# tick-controller-mk-2.net
KiCad netlist of a schematic drawn in EAGLE
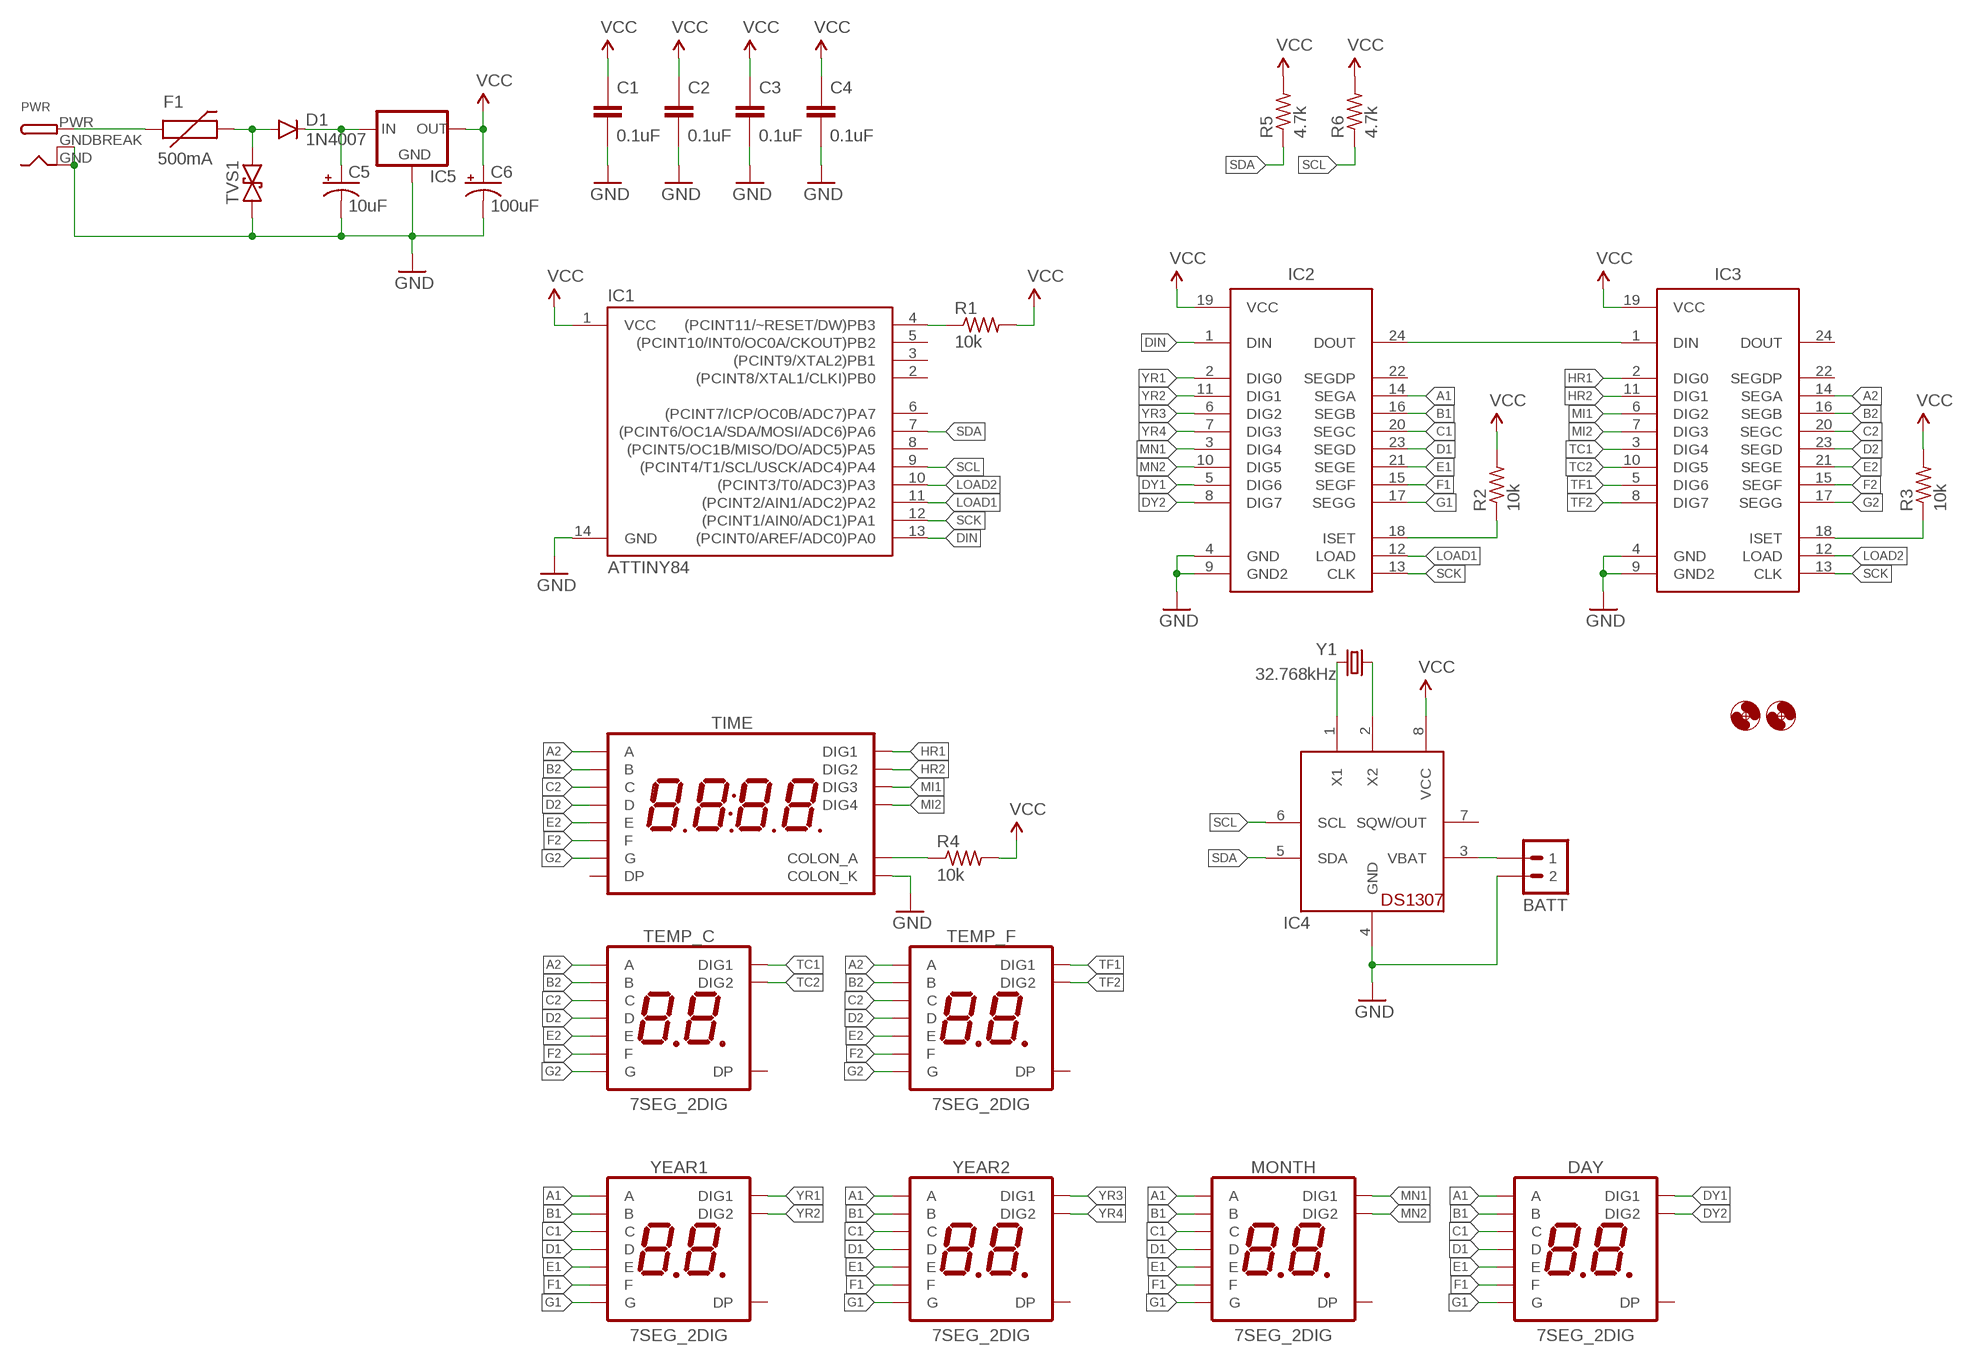
[diagram p0: schematic, sheet 1]

(export (version "E")
  (design (tool "Eeschema 10.0.6"))
  (components
    (comp (ref "BATT")
      (value "M02JST-PTH-VERT")
      (footprint "eagle-import:JST-2-PH-VERT-PTH")
      (libsource (lib "eagle-import") (part "M02JST-PTH-VERT"))
    )
    (comp (ref "C1")
      (value "0.1uF")
      (footprint "eagle-import:C025-024X044")
      (libsource (lib "eagle-import") (part "CAPACITOR-CERAMIC025-024X044"))
    )
    (comp (ref "C2")
      (value "0.1uF")
      (footprint "eagle-import:C025-024X044")
      (libsource (lib "eagle-import") (part "CAPACITOR-CERAMIC025-024X044"))
    )
    (comp (ref "C3")
      (value "0.1uF")
      (footprint "eagle-import:C025-024X044")
      (libsource (lib "eagle-import") (part "CAPACITOR-CERAMIC025-024X044"))
    )
    (comp (ref "C4")
      (value "0.1uF")
      (footprint "eagle-import:C025-024X044")
      (libsource (lib "eagle-import") (part "CAPACITOR-CERAMIC025-024X044"))
    )
    (comp (ref "C5")
      (value "10uF")
      (footprint "eagle-import:E2-5")
      (libsource (lib "eagle-import") (part "CAPACITOR-POLARIZEDE2-5"))
    )
    (comp (ref "C6")
      (value "100uF")
      (footprint "eagle-import:E2-5")
      (libsource (lib "eagle-import") (part "CAPACITOR-POLARIZEDE2-5"))
    )
    (comp (ref "D1")
      (value "1N4007")
      (footprint "eagle-import:DIODE-10.16MM")
      (libsource (lib "eagle-import") (part "DIODEPTH-10.68MM"))
    )
    (comp (ref "DAY")
      (value "7SEG_2DIG")
      (footprint "eagle-import:7SEG_2DIG_14MM")
      (libsource (lib "eagle-import") (part "7SEG_2DIG"))
    )
    (comp (ref "F1")
      (value "500mA")
      (footprint "eagle-import:PTC")
      (libsource (lib "eagle-import") (part "PTCPTH"))
    )
    (comp (ref "H1")
      (value "HOLE#2")
      (footprint "eagle-import:HOLE-#2")
      (libsource (lib "eagle-import") (part "HOLE#2"))
    )
    (comp (ref "H2")
      (value "HOLE#2")
      (footprint "eagle-import:HOLE-#2")
      (libsource (lib "eagle-import") (part "HOLE#2"))
    )
    (comp (ref "IC1")
      (value "ATTINY84")
      (footprint "eagle-import:DIL14")
      (libsource (lib "eagle-import") (part "ATTINY84ATTINY84-20PU"))
    )
    (comp (ref "IC2")
      (value "MAX7219")
      (footprint "eagle-import:DIL24")
      (libsource (lib "eagle-import") (part "MAX7219DIP"))
    )
    (comp (ref "IC3")
      (value "MAX7219")
      (footprint "eagle-import:DIL24")
      (libsource (lib "eagle-import") (part "MAX7219DIP"))
    )
    (comp (ref "IC4")
      (value "DS1307")
      (footprint "eagle-import:DIL08")
      (libsource (lib "eagle-import") (part "DS1307"))
    )
    (comp (ref "IC5")
      (value "L7805")
      (footprint "eagle-import:78XXL")
      (libsource (lib "eagle-import") (part "V_REG_78XXSIDE"))
    )
    (comp (ref "MONTH")
      (value "7SEG_2DIG")
      (footprint "eagle-import:7SEG_2DIG_14MM")
      (libsource (lib "eagle-import") (part "7SEG_2DIG"))
    )
    (comp (ref "PWR")
      (value "DCBARRELPTH")
      (footprint "eagle-import:DCJACK_2MM_PTH")
      (libsource (lib "eagle-import") (part "DCBARRELPTH"))
    )
    (comp (ref "R1")
      (value "10k")
      (footprint "eagle-import:RESISTOR-AXIAL-PTH-5.08MM")
      (libsource (lib "eagle-import") (part "RESISTORPTH-AXIAL-5.08MM"))
    )
    (comp (ref "R2")
      (value "10k")
      (footprint "eagle-import:RESISTOR-AXIAL-PTH-5.08MM")
      (libsource (lib "eagle-import") (part "RESISTORPTH-AXIAL-5.08MM"))
    )
    (comp (ref "R3")
      (value "10k")
      (footprint "eagle-import:RESISTOR-AXIAL-PTH-5.08MM")
      (libsource (lib "eagle-import") (part "RESISTORPTH-AXIAL-5.08MM"))
    )
    (comp (ref "R4")
      (value "10k")
      (footprint "eagle-import:RESISTOR-AXIAL-PTH-5.08MM")
      (libsource (lib "eagle-import") (part "RESISTORPTH-AXIAL-5.08MM"))
    )
    (comp (ref "R5")
      (value "4.7k")
      (footprint "eagle-import:RESISTOR-AXIAL-PTH-5.08MM")
      (libsource (lib "eagle-import") (part "RESISTORPTH-AXIAL-5.08MM"))
    )
    (comp (ref "R6")
      (value "4.7k")
      (footprint "eagle-import:RESISTOR-AXIAL-PTH-5.08MM")
      (libsource (lib "eagle-import") (part "RESISTORPTH-AXIAL-5.08MM"))
    )
    (comp (ref "TEMP_C")
      (value "7SEG_2DIG")
      (footprint "eagle-import:7SEG_2DIG_14MM")
      (libsource (lib "eagle-import") (part "7SEG_2DIG"))
    )
    (comp (ref "TEMP_F")
      (value "7SEG_2DIG")
      (footprint "eagle-import:7SEG_2DIG_14MM")
      (libsource (lib "eagle-import") (part "7SEG_2DIG"))
    )
    (comp (ref "TIME")
      (value "7SED_4DIGIT_14MM14.2MM-CC")
      (footprint "eagle-import:7SEG_4DIG")
      (libsource (lib "eagle-import") (part "7SED_4DIGIT_14MM14.2MM-CC"))
    )
    (comp (ref "TVS1")
      (value "TVSDO-41-TVS-BIDIRECTIONAL")
      (footprint "eagle-import:DO-41-TVS")
      (libsource (lib "eagle-import") (part "TVSDO-41-TVS-BIDIRECTIONAL"))
    )
    (comp (ref "Y1")
      (value "32.768kHz")
      (footprint "eagle-import:TC26H")
      (libsource (lib "eagle-import") (part "CRYSTALTC26H"))
    )
    (comp (ref "YEAR1")
      (value "7SEG_2DIG")
      (footprint "eagle-import:7SEG_2DIG_14MM")
      (libsource (lib "eagle-import") (part "7SEG_2DIG"))
    )
    (comp (ref "YEAR2")
      (value "7SEG_2DIG")
      (footprint "eagle-import:7SEG_2DIG_14MM")
      (libsource (lib "eagle-import") (part "7SEG_2DIG"))
    )
  )
  (nets
    (net (code "1") (name "A1") (class "Default")
      (node (ref "DAY") (pin "4") (pinfunction "A_4") (pintype "passive"))
      (node (ref "IC2") (pin "14") (pinfunction "SEGA_14") (pintype "bidirectional"))
      (node (ref "MONTH") (pin "4") (pinfunction "A_4") (pintype "passive"))
      (node (ref "YEAR1") (pin "4") (pinfunction "A_4") (pintype "passive"))
      (node (ref "YEAR2") (pin "4") (pinfunction "A_4") (pintype "passive"))
    )
    (net (code "2") (name "A2") (class "Default")
      (node (ref "IC3") (pin "14") (pinfunction "SEGA_14") (pintype "bidirectional"))
      (node (ref "TEMP_C") (pin "4") (pinfunction "A_4") (pintype "passive"))
      (node (ref "TEMP_F") (pin "4") (pinfunction "A_4") (pintype "passive"))
      (node (ref "TIME") (pin "P$13") (pinfunction "A_P$13") (pintype "passive"))
    )
    (net (code "3") (name "B1") (class "Default")
      (node (ref "DAY") (pin "3") (pinfunction "B_3") (pintype "passive"))
      (node (ref "IC2") (pin "16") (pinfunction "SEGB_16") (pintype "bidirectional"))
      (node (ref "MONTH") (pin "3") (pinfunction "B_3") (pintype "passive"))
      (node (ref "YEAR1") (pin "3") (pinfunction "B_3") (pintype "passive"))
      (node (ref "YEAR2") (pin "3") (pinfunction "B_3") (pintype "passive"))
    )
    (net (code "4") (name "B2") (class "Default")
      (node (ref "IC3") (pin "16") (pinfunction "SEGB_16") (pintype "bidirectional"))
      (node (ref "TEMP_C") (pin "3") (pinfunction "B_3") (pintype "passive"))
      (node (ref "TEMP_F") (pin "3") (pinfunction "B_3") (pintype "passive"))
      (node (ref "TIME") (pin "P$9") (pinfunction "B_P$9") (pintype "passive"))
    )
    (net (code "5") (name "C1") (class "Default")
      (node (ref "DAY") (pin "9") (pinfunction "C_9") (pintype "passive"))
      (node (ref "IC2") (pin "20") (pinfunction "SEGC_20") (pintype "bidirectional"))
      (node (ref "MONTH") (pin "9") (pinfunction "C_9") (pintype "passive"))
      (node (ref "YEAR1") (pin "9") (pinfunction "C_9") (pintype "passive"))
      (node (ref "YEAR2") (pin "9") (pinfunction "C_9") (pintype "passive"))
    )
    (net (code "6") (name "C2") (class "Default")
      (node (ref "IC3") (pin "20") (pinfunction "SEGC_20") (pintype "bidirectional"))
      (node (ref "TEMP_C") (pin "9") (pinfunction "C_9") (pintype "passive"))
      (node (ref "TEMP_F") (pin "9") (pinfunction "C_9") (pintype "passive"))
      (node (ref "TIME") (pin "P$4") (pinfunction "C_P$4") (pintype "passive"))
    )
    (net (code "7") (name "D1") (class "Default")
      (node (ref "DAY") (pin "8") (pinfunction "D_8") (pintype "passive"))
      (node (ref "IC2") (pin "23") (pinfunction "SEGD_23") (pintype "bidirectional"))
      (node (ref "MONTH") (pin "8") (pinfunction "D_8") (pintype "passive"))
      (node (ref "YEAR1") (pin "8") (pinfunction "D_8") (pintype "passive"))
      (node (ref "YEAR2") (pin "8") (pinfunction "D_8") (pintype "passive"))
    )
    (net (code "8") (name "D2") (class "Default")
      (node (ref "IC3") (pin "23") (pinfunction "SEGD_23") (pintype "bidirectional"))
      (node (ref "TEMP_C") (pin "8") (pinfunction "D_8") (pintype "passive"))
      (node (ref "TEMP_F") (pin "8") (pinfunction "D_8") (pintype "passive"))
      (node (ref "TIME") (pin "P$2") (pinfunction "D_P$2") (pintype "passive"))
    )
    (net (code "9") (name "DIN") (class "Default")
      (node (ref "IC1") (pin "13") (pinfunction "(PCINT0/AREF/ADC0)PA0_13") (pintype "bidirectional"))
      (node (ref "IC2") (pin "1") (pinfunction "DIN_1") (pintype "bidirectional"))
    )
    (net (code "10") (name "DY1") (class "Default")
      (node (ref "DAY") (pin "5") (pinfunction "DIG1_5") (pintype "passive"))
      (node (ref "IC2") (pin "5") (pinfunction "DIG6_5") (pintype "bidirectional"))
    )
    (net (code "11") (name "DY2") (class "Default")
      (node (ref "DAY") (pin "10") (pinfunction "DIG2_10") (pintype "passive"))
      (node (ref "IC2") (pin "8") (pinfunction "DIG7_8") (pintype "bidirectional"))
    )
    (net (code "12") (name "E1") (class "Default")
      (node (ref "DAY") (pin "6") (pinfunction "E_6") (pintype "passive"))
      (node (ref "IC2") (pin "21") (pinfunction "SEGE_21") (pintype "bidirectional"))
      (node (ref "MONTH") (pin "6") (pinfunction "E_6") (pintype "passive"))
      (node (ref "YEAR1") (pin "6") (pinfunction "E_6") (pintype "passive"))
      (node (ref "YEAR2") (pin "6") (pinfunction "E_6") (pintype "passive"))
    )
    (net (code "13") (name "E2") (class "Default")
      (node (ref "IC3") (pin "21") (pinfunction "SEGE_21") (pintype "bidirectional"))
      (node (ref "TEMP_C") (pin "6") (pinfunction "E_6") (pintype "passive"))
      (node (ref "TEMP_F") (pin "6") (pinfunction "E_6") (pintype "passive"))
      (node (ref "TIME") (pin "P$1") (pinfunction "E_P$1") (pintype "passive"))
    )
    (net (code "14") (name "F1") (class "Default")
      (node (ref "DAY") (pin "7") (pinfunction "F_7") (pintype "passive"))
      (node (ref "IC2") (pin "15") (pinfunction "SEGF_15") (pintype "bidirectional"))
      (node (ref "MONTH") (pin "7") (pinfunction "F_7") (pintype "passive"))
      (node (ref "YEAR1") (pin "7") (pinfunction "F_7") (pintype "passive"))
      (node (ref "YEAR2") (pin "7") (pinfunction "F_7") (pintype "passive"))
    )
    (net (code "15") (name "F2") (class "Default")
      (node (ref "IC3") (pin "15") (pinfunction "SEGF_15") (pintype "bidirectional"))
      (node (ref "TEMP_C") (pin "7") (pinfunction "F_7") (pintype "passive"))
      (node (ref "TEMP_F") (pin "7") (pinfunction "F_7") (pintype "passive"))
      (node (ref "TIME") (pin "P$12") (pinfunction "F_P$12") (pintype "passive"))
    )
    (net (code "16") (name "G1") (class "Default")
      (node (ref "DAY") (pin "1") (pinfunction "G_1") (pintype "passive"))
      (node (ref "IC2") (pin "17") (pinfunction "SEGG_17") (pintype "bidirectional"))
      (node (ref "MONTH") (pin "1") (pinfunction "G_1") (pintype "passive"))
      (node (ref "YEAR1") (pin "1") (pinfunction "G_1") (pintype "passive"))
      (node (ref "YEAR2") (pin "1") (pinfunction "G_1") (pintype "passive"))
    )
    (net (code "17") (name "G2") (class "Default")
      (node (ref "IC3") (pin "17") (pinfunction "SEGG_17") (pintype "bidirectional"))
      (node (ref "TEMP_C") (pin "1") (pinfunction "G_1") (pintype "passive"))
      (node (ref "TEMP_F") (pin "1") (pinfunction "G_1") (pintype "passive"))
      (node (ref "TIME") (pin "P$5") (pinfunction "G_P$5") (pintype "passive"))
    )
    (net (code "18") (name "GND") (class "Default")
      (node (ref "BATT") (pin "2") (pinfunction "2_2") (pintype "passive"))
      (node (ref "C1") (pin "2") (pinfunction "2_2") (pintype "passive"))
      (node (ref "C2") (pin "2") (pinfunction "2_2") (pintype "passive"))
      (node (ref "C3") (pin "2") (pinfunction "2_2") (pintype "passive"))
      (node (ref "C4") (pin "2") (pinfunction "2_2") (pintype "passive"))
      (node (ref "C5") (pin "-") (pinfunction "-_-") (pintype "passive"))
      (node (ref "C6") (pin "-") (pinfunction "-_-") (pintype "passive"))
      (node (ref "IC1") (pin "14") (pinfunction "GND_14") (pintype "bidirectional"))
      (node (ref "IC2") (pin "4") (pinfunction "GND_4") (pintype "bidirectional"))
      (node (ref "IC2") (pin "9") (pinfunction "GND2_9") (pintype "bidirectional"))
      (node (ref "IC3") (pin "4") (pinfunction "GND_4") (pintype "bidirectional"))
      (node (ref "IC3") (pin "9") (pinfunction "GND2_9") (pintype "bidirectional"))
      (node (ref "IC4") (pin "4") (pinfunction "GND_4") (pintype "power_in"))
      (node (ref "IC5") (pin "GND") (pinfunction "GND_GND") (pintype "input"))
      (node (ref "PWR") (pin "GND") (pinfunction "GND_GND") (pintype "power_in"))
      (node (ref "PWR") (pin "GNDBREAK") (pinfunction "GNDBREAK_GNDBREAK") (pintype "power_in"))
      (node (ref "TIME") (pin "P$7") (pinfunction "COLON_K_P$7") (pintype "passive"))
      (node (ref "TVS1") (pin "P$1") (pinfunction "1_P$1") (pintype "passive"))
    )
    (net (code "19") (name "HR1") (class "Default")
      (node (ref "IC3") (pin "2") (pinfunction "DIG0_2") (pintype "bidirectional"))
      (node (ref "TIME") (pin "P$14") (pinfunction "DIG1_P$14") (pintype "passive"))
    )
    (net (code "20") (name "HR2") (class "Default")
      (node (ref "IC3") (pin "11") (pinfunction "DIG1_11") (pintype "bidirectional"))
      (node (ref "TIME") (pin "P$11") (pinfunction "DIG2_P$11") (pintype "passive"))
    )
    (net (code "21") (name "LOAD1") (class "Default")
      (node (ref "IC1") (pin "11") (pinfunction "(PCINT2/AIN1/ADC2)PA2_11") (pintype "bidirectional"))
      (node (ref "IC2") (pin "12") (pinfunction "LOAD_12") (pintype "bidirectional"))
    )
    (net (code "22") (name "LOAD2") (class "Default")
      (node (ref "IC1") (pin "10") (pinfunction "(PCINT3/T0/ADC3)PA3_10") (pintype "bidirectional"))
      (node (ref "IC3") (pin "12") (pinfunction "LOAD_12") (pintype "bidirectional"))
    )
    (net (code "23") (name "MI1") (class "Default")
      (node (ref "IC3") (pin "6") (pinfunction "DIG2_6") (pintype "bidirectional"))
      (node (ref "TIME") (pin "P$10") (pinfunction "DIG3_P$10") (pintype "passive"))
    )
    (net (code "24") (name "MI2") (class "Default")
      (node (ref "IC3") (pin "7") (pinfunction "DIG3_7") (pintype "bidirectional"))
      (node (ref "TIME") (pin "P$6") (pinfunction "DIG4_P$6") (pintype "passive"))
    )
    (net (code "25") (name "MN1") (class "Default")
      (node (ref "IC2") (pin "3") (pinfunction "DIG4_3") (pintype "bidirectional"))
      (node (ref "MONTH") (pin "5") (pinfunction "DIG1_5") (pintype "passive"))
    )
    (net (code "26") (name "MN2") (class "Default")
      (node (ref "IC2") (pin "10") (pinfunction "DIG5_10") (pintype "bidirectional"))
      (node (ref "MONTH") (pin "10") (pinfunction "DIG2_10") (pintype "passive"))
    )
    (net (code "27") (name "Net-(C5-Pad+)") (class "Default")
      (node (ref "C5") (pin "+") (pinfunction "+_+") (pintype "passive"))
      (node (ref "D1") (pin "C") (pinfunction "C_C") (pintype "passive"))
      (node (ref "IC5") (pin "IN") (pinfunction "IN_IN") (pintype "input"))
    )
    (net (code "28") (name "Net-(F1-1)") (class "Default")
      (node (ref "F1") (pin "P$1") (pinfunction "1_P$1") (pintype "bidirectional"))
      (node (ref "PWR") (pin "PWR") (pinfunction "PWR_PWR") (pintype "power_in"))
    )
    (net (code "29") (name "Net-(F1-2)") (class "Default")
      (node (ref "D1") (pin "A") (pinfunction "A_A") (pintype "passive"))
      (node (ref "F1") (pin "P$2") (pinfunction "2_P$2") (pintype "bidirectional"))
      (node (ref "TVS1") (pin "P$2") (pinfunction "2_P$2") (pintype "passive"))
    )
    (net (code "30") (name "Net-(IC1-(PCINT11{slash}~{RESET{slash}DW})PB3)") (class "Default")
      (node (ref "IC1") (pin "4") (pinfunction "(PCINT11/~{RESET/DW})PB3_4") (pintype "bidirectional"))
      (node (ref "R1") (pin "P$1") (pinfunction "1_P$1") (pintype "passive"))
    )
    (net (code "31") (name "Net-(IC2-DOUT)") (class "Default")
      (node (ref "IC2") (pin "24") (pinfunction "DOUT_24") (pintype "bidirectional"))
      (node (ref "IC3") (pin "1") (pinfunction "DIN_1") (pintype "bidirectional"))
    )
    (net (code "32") (name "Net-(IC2-ISET)") (class "Default")
      (node (ref "IC2") (pin "18") (pinfunction "ISET_18") (pintype "bidirectional"))
      (node (ref "R2") (pin "P$1") (pinfunction "1_P$1") (pintype "passive"))
    )
    (net (code "33") (name "Net-(IC3-ISET)") (class "Default")
      (node (ref "IC3") (pin "18") (pinfunction "ISET_18") (pintype "bidirectional"))
      (node (ref "R3") (pin "P$1") (pinfunction "1_P$1") (pintype "passive"))
    )
    (net (code "34") (name "Net-(IC4-VBAT)") (class "Default")
      (node (ref "BATT") (pin "1") (pinfunction "1_1") (pintype "passive"))
      (node (ref "IC4") (pin "3") (pinfunction "VBAT_3") (pintype "power_in"))
    )
    (net (code "35") (name "Net-(IC4-X1)") (class "Default")
      (node (ref "IC4") (pin "1") (pinfunction "X1_1") (pintype "passive"))
      (node (ref "Y1") (pin "2") (pinfunction "2_2") (pintype "passive"))
    )
    (net (code "36") (name "Net-(IC4-X2)") (class "Default")
      (node (ref "IC4") (pin "2") (pinfunction "X2_2") (pintype "passive"))
      (node (ref "Y1") (pin "1") (pinfunction "1_1") (pintype "passive"))
    )
    (net (code "37") (name "Net-(R4-1)") (class "Default")
      (node (ref "R4") (pin "P$1") (pinfunction "1_P$1") (pintype "passive"))
      (node (ref "TIME") (pin "P$8") (pinfunction "COLON_A_P$8") (pintype "passive"))
    )
    (net (code "38") (name "SCK") (class "Default")
      (node (ref "IC1") (pin "12") (pinfunction "(PCINT1/AIN0/ADC1)PA1_12") (pintype "bidirectional"))
      (node (ref "IC2") (pin "13") (pinfunction "CLK_13") (pintype "bidirectional"))
      (node (ref "IC3") (pin "13") (pinfunction "CLK_13") (pintype "bidirectional"))
    )
    (net (code "39") (name "SCL") (class "Default")
      (node (ref "IC1") (pin "9") (pinfunction "(PCINT4/T1/SCL/USCK/ADC4)PA4_9") (pintype "bidirectional"))
      (node (ref "IC4") (pin "6") (pinfunction "SCL_6") (pintype "bidirectional"))
      (node (ref "R6") (pin "P$1") (pinfunction "1_P$1") (pintype "passive"))
    )
    (net (code "40") (name "SDA") (class "Default")
      (node (ref "IC1") (pin "7") (pinfunction "(PCINT6/OC1A/SDA/MOSI/ADC6)PA6_7") (pintype "bidirectional"))
      (node (ref "IC4") (pin "5") (pinfunction "SDA_5") (pintype "bidirectional"))
      (node (ref "R5") (pin "P$1") (pinfunction "1_P$1") (pintype "passive"))
    )
    (net (code "41") (name "TC1") (class "Default")
      (node (ref "IC3") (pin "3") (pinfunction "DIG4_3") (pintype "bidirectional"))
      (node (ref "TEMP_C") (pin "5") (pinfunction "DIG1_5") (pintype "passive"))
    )
    (net (code "42") (name "TC2") (class "Default")
      (node (ref "IC3") (pin "10") (pinfunction "DIG5_10") (pintype "bidirectional"))
      (node (ref "TEMP_C") (pin "10") (pinfunction "DIG2_10") (pintype "passive"))
    )
    (net (code "43") (name "TF1") (class "Default")
      (node (ref "IC3") (pin "5") (pinfunction "DIG6_5") (pintype "bidirectional"))
      (node (ref "TEMP_F") (pin "5") (pinfunction "DIG1_5") (pintype "passive"))
    )
    (net (code "44") (name "TF2") (class "Default")
      (node (ref "IC3") (pin "8") (pinfunction "DIG7_8") (pintype "bidirectional"))
      (node (ref "TEMP_F") (pin "10") (pinfunction "DIG2_10") (pintype "passive"))
    )
    (net (code "45") (name "VCC") (class "Default")
      (node (ref "C1") (pin "1") (pinfunction "1_1") (pintype "passive"))
      (node (ref "C2") (pin "1") (pinfunction "1_1") (pintype "passive"))
      (node (ref "C3") (pin "1") (pinfunction "1_1") (pintype "passive"))
      (node (ref "C4") (pin "1") (pinfunction "1_1") (pintype "passive"))
      (node (ref "C6") (pin "+") (pinfunction "+_+") (pintype "passive"))
      (node (ref "IC1") (pin "1") (pinfunction "VCC_1") (pintype "bidirectional"))
      (node (ref "IC2") (pin "19") (pinfunction "VCC_19") (pintype "bidirectional"))
      (node (ref "IC3") (pin "19") (pinfunction "VCC_19") (pintype "bidirectional"))
      (node (ref "IC4") (pin "8") (pinfunction "VCC_8") (pintype "power_in"))
      (node (ref "IC5") (pin "OUT") (pinfunction "OUT_OUT") (pintype "output"))
      (node (ref "R1") (pin "P$2") (pinfunction "2_P$2") (pintype "passive"))
      (node (ref "R2") (pin "P$2") (pinfunction "2_P$2") (pintype "passive"))
      (node (ref "R3") (pin "P$2") (pinfunction "2_P$2") (pintype "passive"))
      (node (ref "R4") (pin "P$2") (pinfunction "2_P$2") (pintype "passive"))
      (node (ref "R5") (pin "P$2") (pinfunction "2_P$2") (pintype "passive"))
      (node (ref "R6") (pin "P$2") (pinfunction "2_P$2") (pintype "passive"))
    )
    (net (code "46") (name "YR1") (class "Default")
      (node (ref "IC2") (pin "2") (pinfunction "DIG0_2") (pintype "bidirectional"))
      (node (ref "YEAR1") (pin "5") (pinfunction "DIG1_5") (pintype "passive"))
    )
    (net (code "47") (name "YR2") (class "Default")
      (node (ref "IC2") (pin "11") (pinfunction "DIG1_11") (pintype "bidirectional"))
      (node (ref "YEAR1") (pin "10") (pinfunction "DIG2_10") (pintype "passive"))
    )
    (net (code "48") (name "YR3") (class "Default")
      (node (ref "IC2") (pin "6") (pinfunction "DIG2_6") (pintype "bidirectional"))
      (node (ref "YEAR2") (pin "5") (pinfunction "DIG1_5") (pintype "passive"))
    )
    (net (code "49") (name "YR4") (class "Default")
      (node (ref "IC2") (pin "7") (pinfunction "DIG3_7") (pintype "bidirectional"))
      (node (ref "YEAR2") (pin "10") (pinfunction "DIG2_10") (pintype "passive"))
    )
    (net (code "50") (name "unconnected-(DAY-DP-Pad2)") (class "Default")
      (node (ref "DAY") (pin "2") (pinfunction "DP_2") (pintype "passive"))
    )
    (net (code "51") (name "unconnected-(IC1-(PCINT5{slash}OC1B{slash}MISO{slash}DO{slash}ADC5)PA5-Pad8)") (class "Default")
      (node (ref "IC1") (pin "8") (pinfunction "(PCINT5/OC1B/MISO/DO/ADC5)PA5_8") (pintype "bidirectional"))
    )
    (net (code "52") (name "unconnected-(IC1-(PCINT7{slash}ICP{slash}OC0B{slash}ADC7)PA7-Pad6)") (class "Default")
      (node (ref "IC1") (pin "6") (pinfunction "(PCINT7/ICP/OC0B/ADC7)PA7_6") (pintype "bidirectional"))
    )
    (net (code "53") (name "unconnected-(IC1-(PCINT8{slash}XTAL1{slash}CLKI)PB0-Pad2)") (class "Default")
      (node (ref "IC1") (pin "2") (pinfunction "(PCINT8/XTAL1/CLKI)PB0_2") (pintype "bidirectional"))
    )
    (net (code "54") (name "unconnected-(IC1-(PCINT9{slash}XTAL2)PB1-Pad3)") (class "Default")
      (node (ref "IC1") (pin "3") (pinfunction "(PCINT9/XTAL2)PB1_3") (pintype "bidirectional"))
    )
    (net (code "55") (name "unconnected-(IC1-(PCINT10{slash}INT0{slash}OC0A{slash}CKOUT)PB2-Pad5)") (class "Default")
      (node (ref "IC1") (pin "5") (pinfunction "(PCINT10/INT0/OC0A/CKOUT)PB2_5") (pintype "bidirectional"))
    )
    (net (code "56") (name "unconnected-(IC2-SEGDP-Pad22)") (class "Default")
      (node (ref "IC2") (pin "22") (pinfunction "SEGDP_22") (pintype "bidirectional"))
    )
    (net (code "57") (name "unconnected-(IC3-DOUT-Pad24)") (class "Default")
      (node (ref "IC3") (pin "24") (pinfunction "DOUT_24") (pintype "bidirectional"))
    )
    (net (code "58") (name "unconnected-(IC3-SEGDP-Pad22)") (class "Default")
      (node (ref "IC3") (pin "22") (pinfunction "SEGDP_22") (pintype "bidirectional"))
    )
    (net (code "59") (name "unconnected-(IC4-SQW{slash}OUT-Pad7)") (class "Default")
      (node (ref "IC4") (pin "7") (pinfunction "SQW/OUT_7") (pintype "bidirectional"))
    )
    (net (code "60") (name "unconnected-(MONTH-DP-Pad2)") (class "Default")
      (node (ref "MONTH") (pin "2") (pinfunction "DP_2") (pintype "passive"))
    )
    (net (code "61") (name "unconnected-(TEMP_C-DP-Pad2)") (class "Default")
      (node (ref "TEMP_C") (pin "2") (pinfunction "DP_2") (pintype "passive"))
    )
    (net (code "62") (name "unconnected-(TEMP_F-DP-Pad2)") (class "Default")
      (node (ref "TEMP_F") (pin "2") (pinfunction "DP_2") (pintype "passive"))
    )
    (net (code "63") (name "unconnected-(TIME-DP-PadP$3)") (class "Default")
      (node (ref "TIME") (pin "P$3") (pinfunction "DP_P$3") (pintype "passive"))
    )
    (net (code "64") (name "unconnected-(YEAR1-DP-Pad2)") (class "Default")
      (node (ref "YEAR1") (pin "2") (pinfunction "DP_2") (pintype "passive"))
    )
    (net (code "65") (name "unconnected-(YEAR2-DP-Pad2)") (class "Default")
      (node (ref "YEAR2") (pin "2") (pinfunction "DP_2") (pintype "passive"))
    )
  )
)
